# HRF_Board.net
KiCad netlist of a schematic drawn in EAGLE
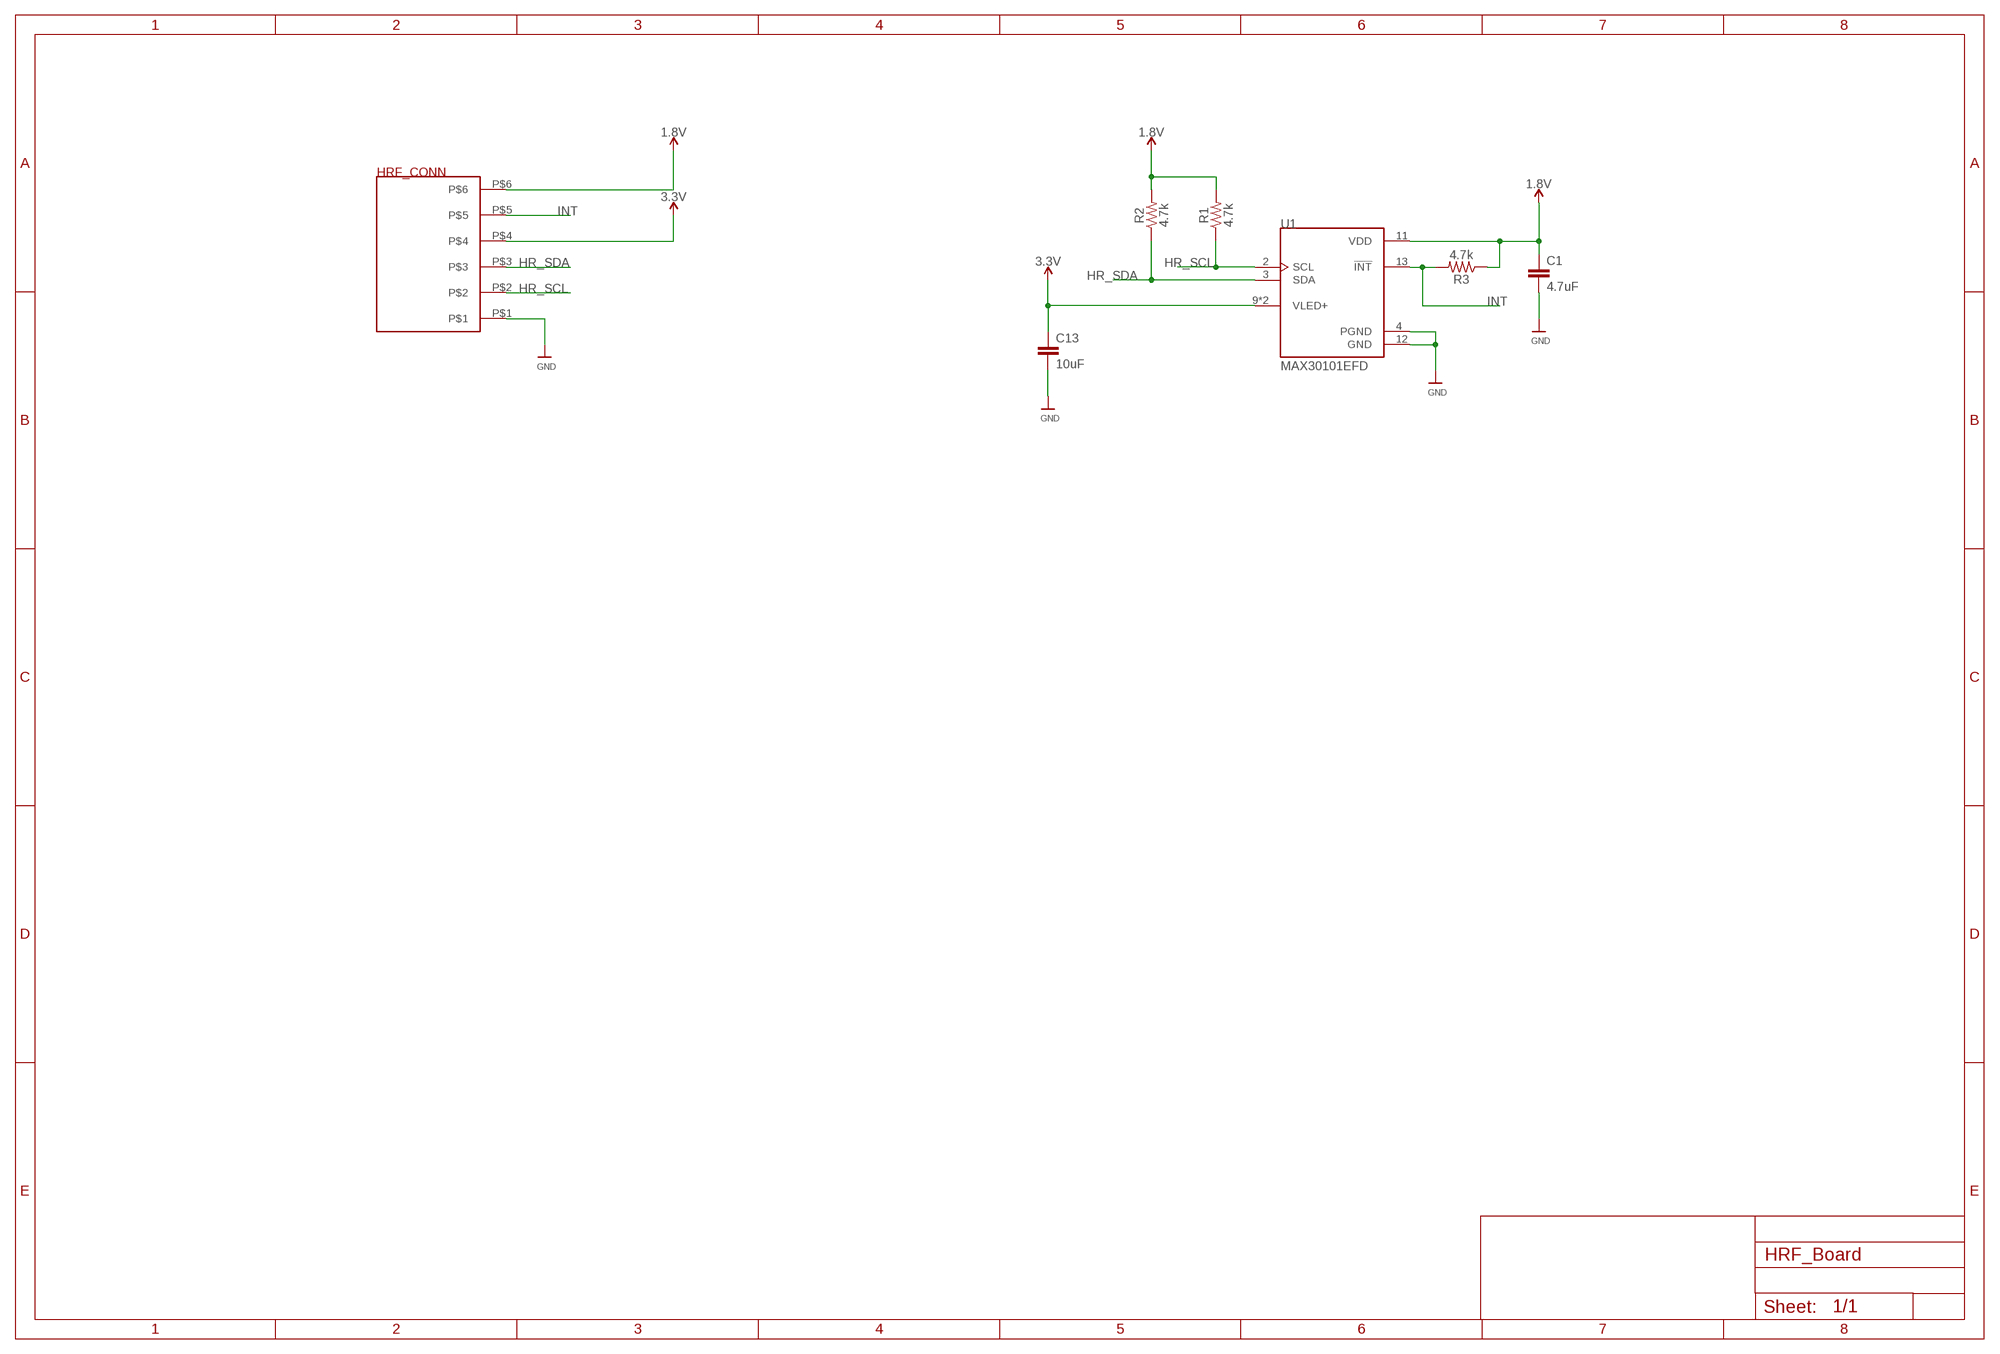
[diagram p0: schematic, sheet 1]

(export (version "E")
  (design (tool "Eeschema 10.0.6"))
  (components
    (comp (ref "C1")
      (value "4.7uF")
      (footprint "eagle-import:0603")
      (libsource (lib "eagle-import") (part "1.0UF-0603-16V-10%"))
    )
    (comp (ref "C13")
      (value "10uF")
      (footprint "eagle-import:0603")
      (libsource (lib "eagle-import") (part "1.0UF-0603-16V-10%"))
    )
    (comp (ref "R1")
      (value "4.7k")
      (footprint "eagle-import:0603")
      (libsource (lib "eagle-import") (part "100KOHM-0603-1/10W-1%"))
    )
    (comp (ref "R2")
      (value "4.7k")
      (footprint "eagle-import:0603")
      (libsource (lib "eagle-import") (part "100KOHM-0603-1/10W-1%"))
    )
    (comp (ref "R3")
      (value "4.7k")
      (footprint "eagle-import:0603")
      (libsource (lib "eagle-import") (part "100KOHM-0603-1/10W-1%"))
    )
    (comp (ref "U$1")
      (value "HRF_CONN")
      (footprint "eagle-import:HRF_CONN")
      (libsource (lib "eagle-import") (part "HRF_CONN"))
    )
    (comp (ref "U1")
      (value "MAX30101EFD")
      (footprint "eagle-import:PSON80P560X330X165-14N")
      (fields
        (field (name "DIGI-KEY_PART_NUMBER") "MAX30101EFD+-ND")
        (field (name "MF") "Maxim Integrated")
        (field (name "MP") "MAX30101EFD+")
      )
      (libsource (lib "eagle-import") (part "MAX30101EFD"))
    )
  )
  (nets
    (net (code "1") (name "/HR_SCL") (class "Default")
      (node (ref "R1") (pin "1") (pinfunction "1_1") (pintype "passive"))
      (node (ref "U$1") (pin "P$2") (pinfunction "P$2_P$2") (pintype "bidirectional"))
      (node (ref "U1") (pin "2") (pinfunction "SCL_2") (pintype "input"))
    )
    (net (code "2") (name "/HR_SDA") (class "Default")
      (node (ref "R2") (pin "1") (pinfunction "1_1") (pintype "passive"))
      (node (ref "U$1") (pin "P$3") (pinfunction "P$3_P$3") (pintype "bidirectional"))
      (node (ref "U1") (pin "3") (pinfunction "SDA_3") (pintype "bidirectional"))
    )
    (net (code "3") (name "/INT") (class "Default")
      (node (ref "R3") (pin "2") (pinfunction "2_2") (pintype "passive"))
      (node (ref "U$1") (pin "P$5") (pinfunction "P$5_P$5") (pintype "bidirectional"))
      (node (ref "U1") (pin "13") (pinfunction "~{INT}_13") (pintype "output"))
    )
    (net (code "4") (name "1.8V") (class "Default")
      (node (ref "C1") (pin "1") (pinfunction "1_1") (pintype "passive"))
      (node (ref "R1") (pin "2") (pinfunction "2_2") (pintype "passive"))
      (node (ref "R2") (pin "2") (pinfunction "2_2") (pintype "passive"))
      (node (ref "R3") (pin "1") (pinfunction "1_1") (pintype "passive"))
      (node (ref "U$1") (pin "P$6") (pinfunction "P$6_P$6") (pintype "bidirectional"))
      (node (ref "U1") (pin "11") (pinfunction "VDD_11") (pintype "power_in"))
    )
    (net (code "5") (name "3.3V") (class "Default")
      (node (ref "C13") (pin "1") (pinfunction "1_1") (pintype "passive"))
      (node (ref "U$1") (pin "P$4") (pinfunction "P$4_P$4") (pintype "bidirectional"))
      (node (ref "U1") (pin "10") (pinfunction "VLED+_10") (pintype "passive"))
      (node (ref "U1") (pin "9") (pinfunction "VLED+_9") (pintype "passive"))
    )
    (net (code "6") (name "GND") (class "Default")
      (node (ref "C1") (pin "2") (pinfunction "2_2") (pintype "passive"))
      (node (ref "C13") (pin "2") (pinfunction "2_2") (pintype "passive"))
      (node (ref "U$1") (pin "P$1") (pinfunction "P$1_P$1") (pintype "bidirectional"))
      (node (ref "U1") (pin "12") (pinfunction "GND_12") (pintype "power_in"))
      (node (ref "U1") (pin "4") (pinfunction "PGND_4") (pintype "power_in"))
    )
  )
)
